# 5V_LDO.net
KiCad netlist of a schematic drawn in Altium Designer
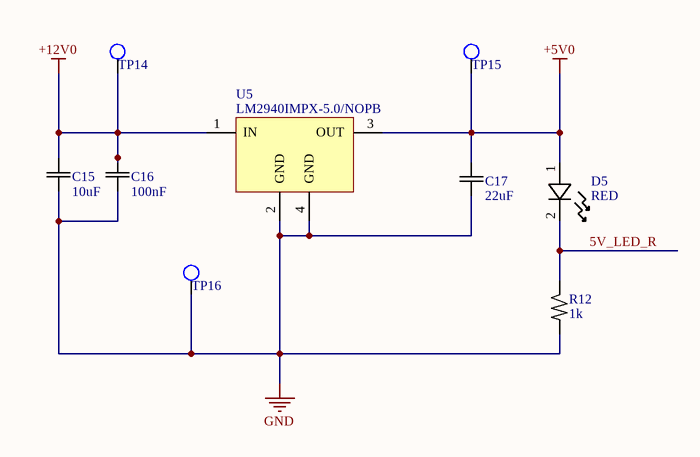
[diagram p0: 5V LDO.SchDoc]

(export (version "E")
  (design (tool "Eeschema 10.0.6"))
  (components
    (comp (ref "C15")
      (value "10uF")
      (footprint "C1206")
      (description "CAP CER 10uF 25V X7R 1206")
      (fields (field (name "MF") "SAMWHA") (field (name "MP") "CS3216X7R106K250NRI"))
      (libsource (lib "Components") (part "Cap_cer"))
    )
    (comp (ref "C16")
      (value "100nF")
      (footprint "C0603")
      (description "CAP CER 100nF 50V X7R 0603")
      (fields (field (name "MF") "HRE") (field (name "MP") "CGA0603X7R104K500JT"))
      (libsource (lib "Components") (part "Cap_cer"))
    )
    (comp (ref "C17")
      (value "22uF")
      (footprint "C1206")
      (description "CAP CER 22uF 10V X7R 1206")
      (fields (field (name "MF") "CCTC") (field (name "MP") "TCC1206X7R226K100HT"))
      (libsource (lib "Components") (part "Cap_cer"))
    )
    (comp (ref "D5")
      (value "RED")
      (footprint "LED0805 RED")
      (description "LED RED WATER CLEAR 0805 SMD")
      (fields (field (name "MF") "XINGLIGHT") (field (name "MP") "XL-TD2012SURC"))
      (libsource (lib "Components") (part "LED"))
    )
    (comp (ref "R12")
      (value "1k")
      (footprint "R0603")
      (description "RES 1kΩ ±5% 100mW 0603")
      (fields (field (name "MF") "VO") (field (name "MP") "SCR0603J1K"))
      (libsource (lib "Components") (part "Res"))
    )
    (comp (ref "TP14")
      (value "TestPoint")
      (footprint "TESTPOINT_SMD_1.27MM")
      (libsource (lib "Components") (part "TestPoint"))
    )
    (comp (ref "TP15")
      (value "TestPoint")
      (footprint "TESTPOINT_SMD_1.27MM")
      (libsource (lib "Components") (part "TestPoint"))
    )
    (comp (ref "TP16")
      (value "TestPoint")
      (footprint "TESTPOINT_SMD_1.27MM")
      (libsource (lib "Components") (part "TestPoint"))
    )
    (comp (ref "U5")
      (value "LM2940IMPX-5.0/NOPB")
      (footprint "SOT-223")
      (fields (field (name "MF") "Texas Instruments"))
      (libsource (lib "Components") (part "LM2940IMPX-5.0/NOPB"))
    )
  )
  (nets
    (net (code "1") (name "+5V0") (class "Default")
      (node (ref "C17") (pin "1") (pinfunction "1_1") (pintype "passive"))
      (node (ref "D5") (pin "1") (pinfunction "1_1") (pintype "passive"))
      (node (ref "TP15") (pin "1") (pinfunction "1_1") (pintype "passive"))
      (node (ref "U5") (pin "3") (pinfunction "OUT_3") (pintype "power_in"))
    )
    (net (code "2") (name "+12V0") (class "Default")
      (node (ref "C15") (pin "2") (pinfunction "2_2") (pintype "passive"))
      (node (ref "C16") (pin "2") (pinfunction "2_2") (pintype "passive"))
      (node (ref "TP14") (pin "1") (pinfunction "1_1") (pintype "passive"))
      (node (ref "U5") (pin "1") (pinfunction "IN_1") (pintype "power_in"))
    )
    (net (code "3") (name "/5V_LED_R") (class "Default")
      (node (ref "D5") (pin "2") (pinfunction "2_2") (pintype "passive"))
      (node (ref "R12") (pin "2") (pinfunction "2_2") (pintype "passive"))
    )
    (net (code "4") (name "GND") (class "Default")
      (node (ref "C15") (pin "1") (pinfunction "1_1") (pintype "passive"))
      (node (ref "C16") (pin "1") (pinfunction "1_1") (pintype "passive"))
      (node (ref "C17") (pin "2") (pinfunction "2_2") (pintype "passive"))
      (node (ref "R12") (pin "1") (pinfunction "1_1") (pintype "passive"))
      (node (ref "TP16") (pin "1") (pinfunction "1_1") (pintype "passive"))
      (node (ref "U5") (pin "2") (pinfunction "GND_2") (pintype "power_in"))
      (node (ref "U5") (pin "4") (pinfunction "GND_4") (pintype "power_in"))
    )
  )
)
